# ioshield.net
KiCad netlist of a schematic drawn in EAGLE
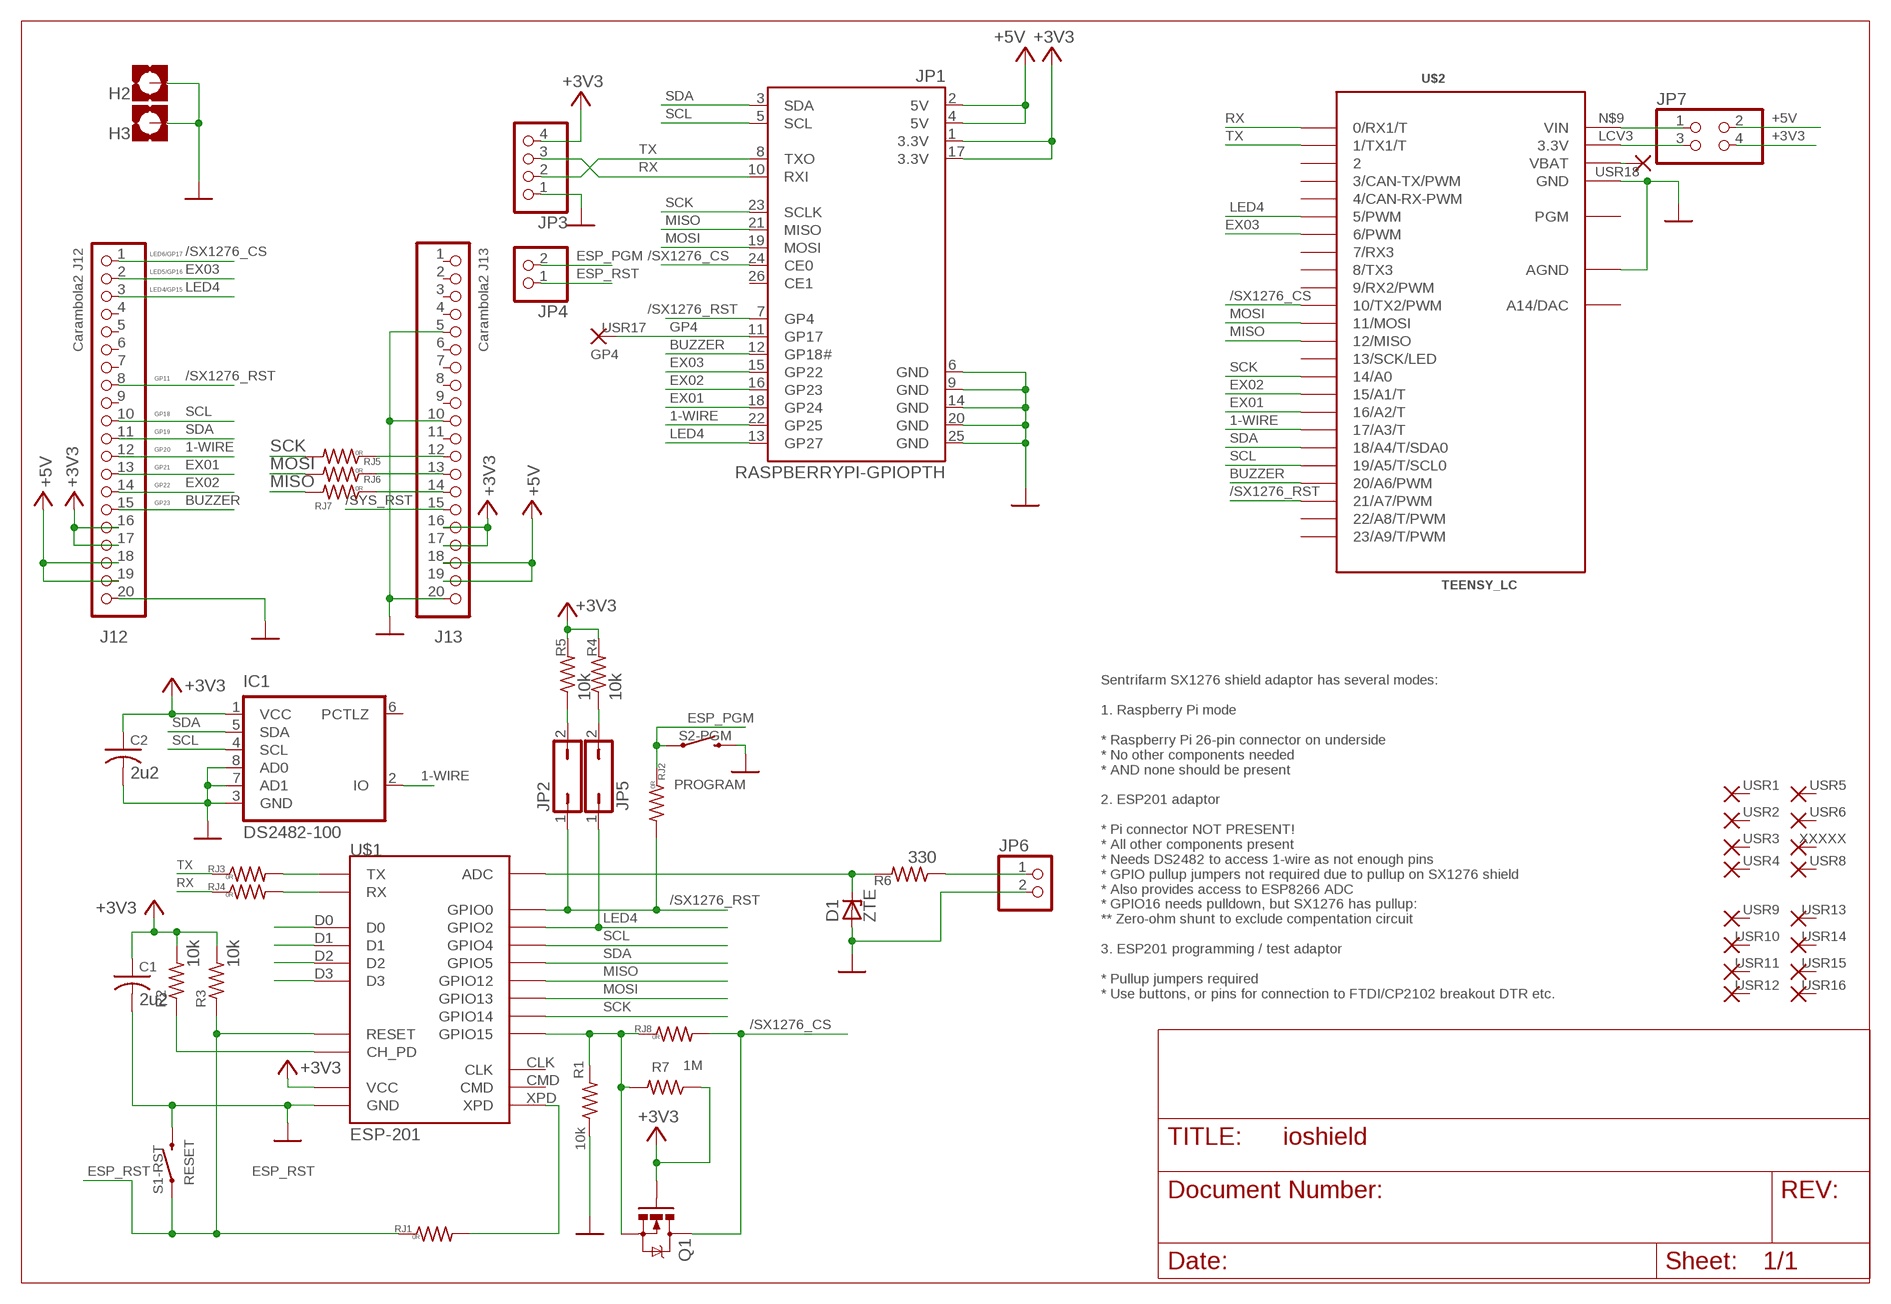
[diagram p0: schematic, sheet 1]

(export (version "E")
  (design (tool "Eeschema 10.0.6"))
  (components
    (comp (ref "C1")
      (value "2u2")
      (footprint "eagle-import:C1206")
      (libsource (lib "eagle-import") (part "C-USC1206"))
    )
    (comp (ref "C2")
      (value "2u2")
      (footprint "eagle-import:C1206")
      (libsource (lib "eagle-import") (part "C-USC1206"))
    )
    (comp (ref "D1")
      (value "ZTE")
      (footprint "eagle-import:DO35Z10")
      (libsource (lib "eagle-import") (part "ZTE"))
    )
    (comp (ref "H2")
      (value "MOUNT-PAD-SQUARE3.2")
      (footprint "eagle-import:3,2-PAD-SQUARE")
      (libsource (lib "eagle-import") (part "MOUNT-PAD-SQUARE3.2"))
    )
    (comp (ref "H3")
      (value "MOUNT-PAD-SQUARE3.2")
      (footprint "eagle-import:3,2-PAD-SQUARE")
      (libsource (lib "eagle-import") (part "MOUNT-PAD-SQUARE3.2"))
    )
    (comp (ref "IC1")
      (value "DS2482-100")
      (footprint "eagle-import:SO08")
      (libsource (lib "eagle-import") (part "DS2482-100"))
    )
    (comp (ref "J12")
      (value "Carambola2 J12")
      (footprint "eagle-import:1X20")
      (libsource (lib "eagle-import") (part "PINHD-1X20"))
    )
    (comp (ref "J13")
      (value "Carambola2 J13")
      (footprint "eagle-import:1X20")
      (libsource (lib "eagle-import") (part "PINHD-1X20"))
    )
    (comp (ref "JP1")
      (value "RASPBERRYPI-GPIOPTH")
      (footprint "eagle-import:2X13-SHROUDED")
      (libsource (lib "eagle-import") (part "RASPBERRYPI-GPIOPTH"))
    )
    (comp (ref "JP2")
      (value "JP1Q")
      (footprint "eagle-import:JP1")
      (libsource (lib "eagle-import") (part "JP1Q"))
    )
    (comp (ref "JP3")
      (value "PINHD-1X4")
      (footprint "eagle-import:1X04")
      (libsource (lib "eagle-import") (part "PINHD-1X4"))
    )
    (comp (ref "JP4")
      (value "PINHD-1X2")
      (footprint "eagle-import:1X02")
      (libsource (lib "eagle-import") (part "PINHD-1X2"))
    )
    (comp (ref "JP5")
      (value "JP1Q")
      (footprint "eagle-import:JP1")
      (libsource (lib "eagle-import") (part "JP1Q"))
    )
    (comp (ref "JP6")
      (value "PINHD-1X2")
      (footprint "eagle-import:1X02")
      (libsource (lib "eagle-import") (part "PINHD-1X2"))
    )
    (comp (ref "JP7")
      (value "PINHD-2X2")
      (footprint "eagle-import:2X02")
      (libsource (lib "eagle-import") (part "PINHD-2X2"))
    )
    (comp (ref "Q1")
      (value "MOSFET-NCHANNEL2N7000")
      (footprint "eagle-import:TO-92")
      (libsource (lib "eagle-import") (part "MOSFET-NCHANNEL2N7000"))
    )
    (comp (ref "R1")
      (value "10k")
      (footprint "eagle-import:M1206")
      (libsource (lib "eagle-import") (part "R-US_M1206"))
    )
    (comp (ref "R2")
      (value "10k")
      (footprint "eagle-import:M1206")
      (libsource (lib "eagle-import") (part "R-US_M1206"))
    )
    (comp (ref "R3")
      (value "10k")
      (footprint "eagle-import:M1206")
      (libsource (lib "eagle-import") (part "R-US_M1206"))
    )
    (comp (ref "R4")
      (value "10k")
      (footprint "eagle-import:M1206")
      (libsource (lib "eagle-import") (part "R-US_M1206"))
    )
    (comp (ref "R5")
      (value "10k")
      (footprint "eagle-import:M1206")
      (libsource (lib "eagle-import") (part "R-US_M1206"))
    )
    (comp (ref "R6")
      (value "330")
      (footprint "eagle-import:M1206")
      (libsource (lib "eagle-import") (part "R-US_M1206"))
    )
    (comp (ref "R7")
      (value "1M")
      (footprint "eagle-import:M1206")
      (libsource (lib "eagle-import") (part "R-US_M1206"))
    )
    (comp (ref "RJ1")
      (value "0R")
      (footprint "eagle-import:M1206")
      (libsource (lib "eagle-import") (part "R-US_M1206"))
    )
    (comp (ref "RJ2")
      (value "0R")
      (footprint "eagle-import:M1206")
      (libsource (lib "eagle-import") (part "R-US_M1206"))
    )
    (comp (ref "RJ3")
      (value "0R")
      (footprint "eagle-import:M1206")
      (libsource (lib "eagle-import") (part "R-US_M1206"))
    )
    (comp (ref "RJ4")
      (value "0R")
      (footprint "eagle-import:M1206")
      (libsource (lib "eagle-import") (part "R-US_M1206"))
    )
    (comp (ref "RJ5")
      (value "0R")
      (footprint "eagle-import:M1206")
      (libsource (lib "eagle-import") (part "R-US_M1206"))
    )
    (comp (ref "RJ6")
      (value "0R")
      (footprint "eagle-import:M1206")
      (libsource (lib "eagle-import") (part "R-US_M1206"))
    )
    (comp (ref "RJ7")
      (value "0R")
      (footprint "eagle-import:M1206")
      (libsource (lib "eagle-import") (part "R-US_M1206"))
    )
    (comp (ref "RJ8")
      (value "0R")
      (footprint "eagle-import:M1206")
      (libsource (lib "eagle-import") (part "R-US_M1206"))
    )
    (comp (ref "S1-RST")
      (value "SWITCH-MOMENTARY-2PTH")
      (footprint "eagle-import:TACTILE-PTH")
      (libsource (lib "eagle-import") (part "SWITCH-MOMENTARY-2PTH"))
    )
    (comp (ref "S2-PGM")
      (value "SWITCH-MOMENTARY-2PTH")
      (footprint "eagle-import:TACTILE-PTH")
      (libsource (lib "eagle-import") (part "SWITCH-MOMENTARY-2PTH"))
    )
    (comp (ref "U$1")
      (value "ESP-201")
      (footprint "eagle-import:ESP-201")
      (libsource (lib "eagle-import") (part "ESP-201"))
    )
    (comp (ref "U$2")
      (value "TEENSY_LC")
      (footprint "eagle-import:TEENSY_3.1_BASIC")
      (libsource (lib "eagle-import") (part "TEENSY_3.1_BASIC"))
    )
    (comp (ref "USR1")
      (value "1,6/0,8")
      (footprint "eagle-import:1,6_0,8")
      (libsource (lib "eagle-import") (part "1,6/0,8"))
    )
    (comp (ref "USR2")
      (value "1,6/0,8")
      (footprint "eagle-import:1,6_0,8")
      (libsource (lib "eagle-import") (part "1,6/0,8"))
    )
    (comp (ref "USR3")
      (value "1,6/0,8")
      (footprint "eagle-import:1,6_0,8")
      (libsource (lib "eagle-import") (part "1,6/0,8"))
    )
    (comp (ref "USR4")
      (value "1,6/0,8")
      (footprint "eagle-import:1,6_0,8")
      (libsource (lib "eagle-import") (part "1,6/0,8"))
    )
    (comp (ref "USR5")
      (value "1,6/0,8")
      (footprint "eagle-import:1,6_0,8")
      (libsource (lib "eagle-import") (part "1,6/0,8"))
    )
    (comp (ref "USR6")
      (value "1,6/0,8")
      (footprint "eagle-import:1,6_0,8")
      (libsource (lib "eagle-import") (part "1,6/0,8"))
    )
    (comp (ref "USR8")
      (value "1,6/0,8")
      (footprint "eagle-import:1,6_0,8")
      (libsource (lib "eagle-import") (part "1,6/0,8"))
    )
    (comp (ref "USR9")
      (value "1,6/0,8")
      (footprint "eagle-import:1,6_0,8")
      (libsource (lib "eagle-import") (part "1,6/0,8"))
    )
    (comp (ref "USR10")
      (value "1,6/0,8")
      (footprint "eagle-import:1,6_0,8")
      (libsource (lib "eagle-import") (part "1,6/0,8"))
    )
    (comp (ref "USR11")
      (value "1,6/0,8")
      (footprint "eagle-import:1,6_0,8")
      (libsource (lib "eagle-import") (part "1,6/0,8"))
    )
    (comp (ref "USR12")
      (value "1,6/0,8")
      (footprint "eagle-import:1,6_0,8")
      (libsource (lib "eagle-import") (part "1,6/0,8"))
    )
    (comp (ref "USR13")
      (value "1,6/0,8")
      (footprint "eagle-import:1,6_0,8")
      (libsource (lib "eagle-import") (part "1,6/0,8"))
    )
    (comp (ref "USR14")
      (value "1,6/0,8")
      (footprint "eagle-import:1,6_0,8")
      (libsource (lib "eagle-import") (part "1,6/0,8"))
    )
    (comp (ref "USR15")
      (value "1,6/0,8")
      (footprint "eagle-import:1,6_0,8")
      (libsource (lib "eagle-import") (part "1,6/0,8"))
    )
    (comp (ref "USR16")
      (value "1,6/0,8")
      (footprint "eagle-import:1,6_0,8")
      (libsource (lib "eagle-import") (part "1,6/0,8"))
    )
    (comp (ref "USR17")
      (value "GP4")
      (footprint "eagle-import:1,6_0,8")
      (libsource (lib "eagle-import") (part "1,6/0,8"))
    )
    (comp (ref "USR18")
      (value "1,6/0,8")
      (footprint "eagle-import:1,6_0,8")
      (libsource (lib "eagle-import") (part "1,6/0,8"))
    )
    (comp (ref "XXXXX")
      (value "1,6/0,8")
      (footprint "eagle-import:1,6_0,8")
      (libsource (lib "eagle-import") (part "1,6/0,8"))
    )
  )
  (nets
    (net (code "1") (name "+3V3") (class "Default")
      (node (ref "C1") (pin "1") (pinfunction "1_1") (pintype "passive"))
      (node (ref "C2") (pin "1") (pinfunction "1_1") (pintype "passive"))
      (node (ref "IC1") (pin "1") (pinfunction "VCC_1") (pintype "power_in"))
      (node (ref "J12") (pin "16") (pinfunction "16_16") (pintype "passive"))
      (node (ref "J12") (pin "17") (pinfunction "17_17") (pintype "passive"))
      (node (ref "J13") (pin "16") (pinfunction "16_16") (pintype "passive"))
      (node (ref "J13") (pin "17") (pinfunction "17_17") (pintype "passive"))
      (node (ref "JP1") (pin "1") (pinfunction "3.3V_1") (pintype "power_in"))
      (node (ref "JP1") (pin "17") (pinfunction "3.3V_17") (pintype "power_in"))
      (node (ref "JP3") (pin "4") (pinfunction "4_4") (pintype "passive"))
      (node (ref "JP7") (pin "4") (pinfunction "4_4") (pintype "passive"))
      (node (ref "Q1") (pin "2") (pinfunction "G_2") (pintype "passive"))
      (node (ref "R2") (pin "2") (pinfunction "2_2") (pintype "passive"))
      (node (ref "R3") (pin "2") (pinfunction "2_2") (pintype "passive"))
      (node (ref "R4") (pin "2") (pinfunction "2_2") (pintype "passive"))
      (node (ref "R5") (pin "2") (pinfunction "2_2") (pintype "passive"))
      (node (ref "R7") (pin "1") (pinfunction "1_1") (pintype "passive"))
      (node (ref "U$1") (pin "3V3") (pinfunction "VCC_3V3") (pintype "bidirectional"))
      (node (ref "U$1") (pin "3V3_2") (pinfunction "VCC_3V3_2") (pintype "bidirectional"))
      (node (ref "U$1") (pin "3V3_3") (pinfunction "VCC_3V3_3") (pintype "bidirectional"))
    )
    (net (code "2") (name "+5V") (class "Default")
      (node (ref "J12") (pin "18") (pinfunction "18_18") (pintype "passive"))
      (node (ref "J12") (pin "19") (pinfunction "19_19") (pintype "passive"))
      (node (ref "J13") (pin "18") (pinfunction "18_18") (pintype "passive"))
      (node (ref "J13") (pin "19") (pinfunction "19_19") (pintype "passive"))
      (node (ref "JP1") (pin "2") (pinfunction "5V_2") (pintype "power_in"))
      (node (ref "JP1") (pin "4") (pinfunction "5V_4") (pintype "power_in"))
      (node (ref "JP7") (pin "2") (pinfunction "2_2") (pintype "passive"))
    )
    (net (code "3") (name "/1-WIRE") (class "Default")
      (node (ref "IC1") (pin "2") (pinfunction "IO_2") (pintype "bidirectional"))
      (node (ref "J12") (pin "12") (pinfunction "12_12") (pintype "passive"))
      (node (ref "JP1") (pin "22") (pinfunction "GP25_22") (pintype "bidirectional"))
      (node (ref "U$2") (pin "17/A3") (pinfunction "17/A3/T_17/A3") (pintype "bidirectional"))
    )
    (net (code "4") (name "/BUZZER") (class "Default")
      (node (ref "J12") (pin "15") (pinfunction "15_15") (pintype "passive"))
      (node (ref "JP1") (pin "12") (pinfunction "GP18#_12") (pintype "bidirectional"))
      (node (ref "U$2") (pin "20/A6") (pinfunction "20/A6/PWM_20/A6") (pintype "bidirectional"))
    )
    (net (code "5") (name "/ESP_PGM") (class "Default")
      (node (ref "JP4") (pin "2") (pinfunction "2_2") (pintype "passive"))
      (node (ref "RJ2") (pin "1") (pinfunction "1_1") (pintype "passive"))
      (node (ref "S2-PGM") (pin "1") (pinfunction "1_1") (pintype "passive"))
    )
    (net (code "6") (name "/ESP_RST") (class "Default")
      (node (ref "JP4") (pin "1") (pinfunction "1_1") (pintype "passive"))
      (node (ref "R3") (pin "1") (pinfunction "1_1") (pintype "passive"))
      (node (ref "RJ1") (pin "1") (pinfunction "1_1") (pintype "passive"))
      (node (ref "S1-RST") (pin "1") (pinfunction "1_1") (pintype "passive"))
      (node (ref "U$1") (pin "RST") (pinfunction "RESET_RST") (pintype "bidirectional"))
    )
    (net (code "7") (name "/EX01") (class "Default")
      (node (ref "J12") (pin "13") (pinfunction "13_13") (pintype "passive"))
      (node (ref "JP1") (pin "18") (pinfunction "GP24_18") (pintype "bidirectional"))
      (node (ref "U$2") (pin "16/A2") (pinfunction "16/A2/T_16/A2") (pintype "bidirectional"))
    )
    (net (code "8") (name "/EX02") (class "Default")
      (node (ref "J12") (pin "14") (pinfunction "14_14") (pintype "passive"))
      (node (ref "JP1") (pin "16") (pinfunction "GP23_16") (pintype "bidirectional"))
      (node (ref "U$2") (pin "15/A1") (pinfunction "15/A1/T_15/A1") (pintype "bidirectional"))
    )
    (net (code "9") (name "/EX03") (class "Default")
      (node (ref "J12") (pin "2") (pinfunction "2_2") (pintype "passive"))
      (node (ref "JP1") (pin "15") (pinfunction "GP22_15") (pintype "bidirectional"))
      (node (ref "U$2") (pin "6") (pinfunction "6/PWM_6") (pintype "bidirectional"))
    )
    (net (code "10") (name "/GP4") (class "Default")
      (node (ref "JP1") (pin "11") (pinfunction "GP17_11") (pintype "bidirectional"))
      (node (ref "USR17") (pin "1") (pinfunction "P_1") (pintype "passive"))
    )
    (net (code "11") (name "/LCV3") (class "Default")
      (node (ref "JP7") (pin "3") (pinfunction "3_3") (pintype "passive"))
      (node (ref "U$2") (pin "3.3V") (pinfunction "3.3V_3.3V") (pintype "power_in"))
      (node (ref "U$2") (pin "3.3V1") (pinfunction "3.3V_3.3V1") (pintype "power_in"))
    )
    (net (code "12") (name "/LED4") (class "Default")
      (node (ref "J12") (pin "3") (pinfunction "3_3") (pintype "passive"))
      (node (ref "JP1") (pin "13") (pinfunction "GP27_13") (pintype "bidirectional"))
      (node (ref "JP5") (pin "1") (pinfunction "1_1") (pintype "passive"))
      (node (ref "U$1") (pin "GPIO2") (pinfunction "GPIO2_GPIO2") (pintype "bidirectional"))
      (node (ref "U$2") (pin "5") (pinfunction "5/PWM_5") (pintype "bidirectional"))
    )
    (net (code "13") (name "/MISO") (class "Default")
      (node (ref "JP1") (pin "21") (pinfunction "MISO_21") (pintype "input"))
      (node (ref "RJ7") (pin "2") (pinfunction "2_2") (pintype "passive"))
      (node (ref "U$1") (pin "GPIO12") (pinfunction "GPIO12_GPIO12") (pintype "bidirectional"))
      (node (ref "U$2") (pin "12") (pinfunction "12/MISO_12") (pintype "bidirectional"))
    )
    (net (code "14") (name "/MOSI") (class "Default")
      (node (ref "JP1") (pin "19") (pinfunction "MOSI_19") (pintype "output"))
      (node (ref "RJ6") (pin "2") (pinfunction "2_2") (pintype "passive"))
      (node (ref "U$1") (pin "GPIO13") (pinfunction "GPIO13_GPIO13") (pintype "bidirectional"))
      (node (ref "U$2") (pin "11") (pinfunction "11/MOSI_11") (pintype "bidirectional"))
    )
    (net (code "15") (name "/N$9") (class "Default")
      (node (ref "JP7") (pin "1") (pinfunction "1_1") (pintype "passive"))
      (node (ref "U$2") (pin "VIN") (pinfunction "VIN_VIN") (pintype "power_in"))
    )
    (net (code "16") (name "/RX") (class "Default")
      (node (ref "JP1") (pin "10") (pinfunction "RXI_10") (pintype "input"))
      (node (ref "JP3") (pin "3") (pinfunction "3_3") (pintype "passive"))
      (node (ref "RJ4") (pin "1") (pinfunction "1_1") (pintype "passive"))
      (node (ref "U$2") (pin "0") (pinfunction "0/RX1/T_0") (pintype "bidirectional"))
    )
    (net (code "17") (name "/SCK") (class "Default")
      (node (ref "JP1") (pin "23") (pinfunction "SCLK_23") (pintype "output"))
      (node (ref "RJ5") (pin "2") (pinfunction "2_2") (pintype "passive"))
      (node (ref "U$1") (pin "GPIO14") (pinfunction "GPIO14_GPIO14") (pintype "bidirectional"))
      (node (ref "U$2") (pin "14/A0") (pinfunction "14/A0_14/A0") (pintype "bidirectional"))
    )
    (net (code "18") (name "/SCL") (class "Default")
      (node (ref "IC1") (pin "4") (pinfunction "SCL_4") (pintype "input"))
      (node (ref "J12") (pin "10") (pinfunction "10_10") (pintype "passive"))
      (node (ref "JP1") (pin "5") (pinfunction "SCL_5") (pintype "bidirectional"))
      (node (ref "U$1") (pin "GPIO4") (pinfunction "GPIO4_GPIO4") (pintype "bidirectional"))
      (node (ref "U$2") (pin "19/A5") (pinfunction "19/A5/T/SCL0_19/A5") (pintype "bidirectional"))
    )
    (net (code "19") (name "/SDA") (class "Default")
      (node (ref "IC1") (pin "5") (pinfunction "SDA_5") (pintype "input"))
      (node (ref "J12") (pin "11") (pinfunction "11_11") (pintype "passive"))
      (node (ref "JP1") (pin "3") (pinfunction "SDA_3") (pintype "bidirectional"))
      (node (ref "U$1") (pin "GPIO5") (pinfunction "GPIO5_GPIO5") (pintype "bidirectional"))
      (node (ref "U$2") (pin "18/A4") (pinfunction "18/A4/T/SDA0_18/A4") (pintype "bidirectional"))
    )
    (net (code "20") (name "/TX") (class "Default")
      (node (ref "JP1") (pin "8") (pinfunction "TXO_8") (pintype "output"))
      (node (ref "JP3") (pin "2") (pinfunction "2_2") (pintype "passive"))
      (node (ref "RJ3") (pin "1") (pinfunction "1_1") (pintype "passive"))
      (node (ref "U$2") (pin "1") (pinfunction "1/TX1/T_1") (pintype "bidirectional"))
    )
    (net (code "21") (name "/{slash}SX1276_CS") (class "Default")
      (node (ref "J12") (pin "1") (pinfunction "1_1") (pintype "passive"))
      (node (ref "JP1") (pin "24") (pinfunction "CE0_24") (pintype "output"))
      (node (ref "Q1") (pin "3") (pinfunction "D_3") (pintype "passive"))
      (node (ref "RJ8") (pin "2") (pinfunction "2_2") (pintype "passive"))
      (node (ref "U$2") (pin "10") (pinfunction "10/TX2/PWM_10") (pintype "bidirectional"))
    )
    (net (code "22") (name "/{slash}SX1276_RST") (class "Default")
      (node (ref "J12") (pin "8") (pinfunction "8_8") (pintype "passive"))
      (node (ref "JP1") (pin "7") (pinfunction "GP4_7") (pintype "bidirectional"))
      (node (ref "JP2") (pin "1") (pinfunction "1_1") (pintype "passive"))
      (node (ref "RJ2") (pin "2") (pinfunction "2_2") (pintype "passive"))
      (node (ref "U$1") (pin "GPIO0") (pinfunction "GPIO0_GPIO0") (pintype "bidirectional"))
      (node (ref "U$2") (pin "21/A7") (pinfunction "21/A7/PWM_21/A7") (pintype "bidirectional"))
    )
    (net (code "23") (name "/{slash}SYS_RST") (class "Default")
      (node (ref "J13") (pin "15") (pinfunction "15_15") (pintype "passive"))
    )
    (net (code "24") (name "GND") (class "Default")
      (node (ref "C1") (pin "2") (pinfunction "2_2") (pintype "passive"))
      (node (ref "C2") (pin "2") (pinfunction "2_2") (pintype "passive"))
      (node (ref "D1") (pin "A") (pinfunction "A_A") (pintype "passive"))
      (node (ref "H2") (pin "B3,2") (pinfunction "MOUNT_B3,2") (pintype "passive"))
      (node (ref "H3") (pin "B3,2") (pinfunction "MOUNT_B3,2") (pintype "passive"))
      (node (ref "IC1") (pin "3") (pinfunction "GND_3") (pintype "power_in"))
      (node (ref "IC1") (pin "7") (pinfunction "AD1_7") (pintype "bidirectional"))
      (node (ref "IC1") (pin "8") (pinfunction "AD0_8") (pintype "bidirectional"))
      (node (ref "J12") (pin "20") (pinfunction "20_20") (pintype "passive"))
      (node (ref "J13") (pin "10") (pinfunction "10_10") (pintype "passive"))
      (node (ref "J13") (pin "20") (pinfunction "20_20") (pintype "passive"))
      (node (ref "J13") (pin "5") (pinfunction "5_5") (pintype "passive"))
      (node (ref "JP1") (pin "14") (pinfunction "GND_14") (pintype "power_in"))
      (node (ref "JP1") (pin "20") (pinfunction "GND_20") (pintype "power_in"))
      (node (ref "JP1") (pin "25") (pinfunction "GND_25") (pintype "power_in"))
      (node (ref "JP1") (pin "6") (pinfunction "GND_6") (pintype "power_in"))
      (node (ref "JP1") (pin "9") (pinfunction "GND_9") (pintype "power_in"))
      (node (ref "JP3") (pin "1") (pinfunction "1_1") (pintype "passive"))
      (node (ref "JP6") (pin "2") (pinfunction "2_2") (pintype "passive"))
      (node (ref "R1") (pin "1") (pinfunction "1_1") (pintype "passive"))
      (node (ref "S1-RST") (pin "3") (pinfunction "2_3") (pintype "passive"))
      (node (ref "S2-PGM") (pin "3") (pinfunction "2_3") (pintype "passive"))
      (node (ref "U$1") (pin "GND") (pinfunction "GND_GND") (pintype "bidirectional"))
      (node (ref "U$1") (pin "GND_2") (pinfunction "GND_GND_2") (pintype "bidirectional"))
      (node (ref "U$1") (pin "GND_3") (pinfunction "GND_GND_3") (pintype "bidirectional"))
      (node (ref "U$2") (pin "AGND") (pinfunction "AGND_AGND") (pintype "power_in"))
      (node (ref "U$2") (pin "GND") (pinfunction "GND_GND") (pintype "power_in"))
      (node (ref "U$2") (pin "GND1") (pinfunction "GND_GND1") (pintype "power_in"))
    )
    (net (code "25") (name "Net-(D1-PadC)") (class "Default")
      (node (ref "D1") (pin "C") (pinfunction "C_C") (pintype "passive"))
      (node (ref "R6") (pin "2") (pinfunction "2_2") (pintype "passive"))
      (node (ref "U$1") (pin "ADC") (pinfunction "ADC_ADC") (pintype "bidirectional"))
    )
    (net (code "26") (name "Net-(J13-Pad12)") (class "Default")
      (node (ref "J13") (pin "12") (pinfunction "12_12") (pintype "passive"))
      (node (ref "RJ5") (pin "1") (pinfunction "1_1") (pintype "passive"))
    )
    (net (code "27") (name "Net-(J13-Pad13)") (class "Default")
      (node (ref "J13") (pin "13") (pinfunction "13_13") (pintype "passive"))
      (node (ref "RJ6") (pin "1") (pinfunction "1_1") (pintype "passive"))
    )
    (net (code "28") (name "Net-(J13-Pad14)") (class "Default")
      (node (ref "J13") (pin "14") (pinfunction "14_14") (pintype "passive"))
      (node (ref "RJ7") (pin "1") (pinfunction "1_1") (pintype "passive"))
    )
    (net (code "29") (name "Net-(JP2-Pad2)") (class "Default")
      (node (ref "JP2") (pin "2") (pinfunction "2_2") (pintype "passive"))
      (node (ref "R5") (pin "1") (pinfunction "1_1") (pintype "passive"))
    )
    (net (code "30") (name "Net-(JP5-Pad2)") (class "Default")
      (node (ref "JP5") (pin "2") (pinfunction "2_2") (pintype "passive"))
      (node (ref "R4") (pin "1") (pinfunction "1_1") (pintype "passive"))
    )
    (net (code "31") (name "Net-(JP6-Pad1)") (class "Default")
      (node (ref "JP6") (pin "1") (pinfunction "1_1") (pintype "passive"))
      (node (ref "R6") (pin "1") (pinfunction "1_1") (pintype "passive"))
    )
    (net (code "32") (name "Net-(Q1-S)") (class "Default")
      (node (ref "Q1") (pin "1") (pinfunction "S_1") (pintype "passive"))
      (node (ref "R1") (pin "2") (pinfunction "2_2") (pintype "passive"))
      (node (ref "R7") (pin "2") (pinfunction "2_2") (pintype "passive"))
      (node (ref "RJ8") (pin "1") (pinfunction "1_1") (pintype "passive"))
      (node (ref "U$1") (pin "GPIO15") (pinfunction "GPIO15_GPIO15") (pintype "bidirectional"))
    )
    (net (code "33") (name "Net-(R2-Pad1)") (class "Default")
      (node (ref "R2") (pin "1") (pinfunction "1_1") (pintype "passive"))
      (node (ref "U$1") (pin "CH_PD") (pinfunction "CH_PD_CH_PD") (pintype "bidirectional"))
    )
    (net (code "34") (name "Net-(RJ1-Pad2)") (class "Default")
      (node (ref "RJ1") (pin "2") (pinfunction "2_2") (pintype "passive"))
      (node (ref "U$1") (pin "XPD") (pinfunction "XPD_XPD") (pintype "bidirectional"))
    )
    (net (code "35") (name "Net-(USR18-P)") (class "Default")
      (node (ref "U$2") (pin "VBAT") (pinfunction "VBAT_VBAT") (pintype "power_in"))
      (node (ref "USR18") (pin "1") (pinfunction "P_1") (pintype "passive"))
    )
    (net (code "36") (name "unconnected-(IC1-PCTLZ-Pad6)") (class "Default")
      (node (ref "IC1") (pin "6") (pinfunction "PCTLZ_6") (pintype "output"))
    )
    (net (code "37") (name "unconnected-(J12-Pad4)") (class "Default")
      (node (ref "J12") (pin "4") (pinfunction "4_4") (pintype "passive"))
    )
    (net (code "38") (name "unconnected-(J12-Pad5)") (class "Default")
      (node (ref "J12") (pin "5") (pinfunction "5_5") (pintype "passive"))
    )
    (net (code "39") (name "unconnected-(J12-Pad6)") (class "Default")
      (node (ref "J12") (pin "6") (pinfunction "6_6") (pintype "passive"))
    )
    (net (code "40") (name "unconnected-(J12-Pad7)") (class "Default")
      (node (ref "J12") (pin "7") (pinfunction "7_7") (pintype "passive"))
    )
    (net (code "41") (name "unconnected-(J12-Pad9)") (class "Default")
      (node (ref "J12") (pin "9") (pinfunction "9_9") (pintype "passive"))
    )
    (net (code "42") (name "unconnected-(J13-Pad1)") (class "Default")
      (node (ref "J13") (pin "1") (pinfunction "1_1") (pintype "passive"))
    )
    (net (code "43") (name "unconnected-(J13-Pad2)") (class "Default")
      (node (ref "J13") (pin "2") (pinfunction "2_2") (pintype "passive"))
    )
    (net (code "44") (name "unconnected-(J13-Pad3)") (class "Default")
      (node (ref "J13") (pin "3") (pinfunction "3_3") (pintype "passive"))
    )
    (net (code "45") (name "unconnected-(J13-Pad4)") (class "Default")
      (node (ref "J13") (pin "4") (pinfunction "4_4") (pintype "passive"))
    )
    (net (code "46") (name "unconnected-(J13-Pad6)") (class "Default")
      (node (ref "J13") (pin "6") (pinfunction "6_6") (pintype "passive"))
    )
    (net (code "47") (name "unconnected-(J13-Pad7)") (class "Default")
      (node (ref "J13") (pin "7") (pinfunction "7_7") (pintype "passive"))
    )
    (net (code "48") (name "unconnected-(J13-Pad8)") (class "Default")
      (node (ref "J13") (pin "8") (pinfunction "8_8") (pintype "passive"))
    )
    (net (code "49") (name "unconnected-(J13-Pad9)") (class "Default")
      (node (ref "J13") (pin "9") (pinfunction "9_9") (pintype "passive"))
    )
    (net (code "50") (name "unconnected-(J13-Pad11)") (class "Default")
      (node (ref "J13") (pin "11") (pinfunction "11_11") (pintype "passive"))
    )
    (net (code "51") (name "unconnected-(JP1-CE1-Pad26)") (class "Default")
      (node (ref "JP1") (pin "26") (pinfunction "CE1_26") (pintype "output"))
    )
    (net (code "52") (name "unconnected-(RJ3-Pad2)") (class "Default")
      (node (ref "RJ3") (pin "2") (pinfunction "2_2") (pintype "passive"))
    )
    (net (code "53") (name "unconnected-(RJ4-Pad2)") (class "Default")
      (node (ref "RJ4") (pin "2") (pinfunction "2_2") (pintype "passive"))
    )
    (net (code "54") (name "unconnected-(U$1-PadCLK)") (class "Default")
      (node (ref "U$1") (pin "CLK") (pinfunction "CLK_CLK") (pintype "bidirectional"))
    )
    (net (code "55") (name "unconnected-(U$1-PadCMD)") (class "Default")
      (node (ref "U$1") (pin "CMD") (pinfunction "CMD_CMD") (pintype "bidirectional"))
    )
    (net (code "56") (name "unconnected-(U$1-PadD0)") (class "Default")
      (node (ref "U$1") (pin "D0") (pinfunction "D0_D0") (pintype "bidirectional"))
    )
    (net (code "57") (name "unconnected-(U$1-PadD1)") (class "Default")
      (node (ref "U$1") (pin "D1") (pinfunction "D1_D1") (pintype "bidirectional"))
    )
    (net (code "58") (name "unconnected-(U$1-PadD2)") (class "Default")
      (node (ref "U$1") (pin "D2") (pinfunction "D2_D2") (pintype "bidirectional"))
    )
    (net (code "59") (name "unconnected-(U$1-PadD3)") (class "Default")
      (node (ref "U$1") (pin "D3") (pinfunction "D3_D3") (pintype "bidirectional"))
    )
    (net (code "60") (name "unconnected-(U$1-PadRX)") (class "Default")
      (node (ref "U$1") (pin "RX") (pinfunction "RX_RX") (pintype "bidirectional"))
    )
    (net (code "61") (name "unconnected-(U$1-PadTX)") (class "Default")
      (node (ref "U$1") (pin "TX") (pinfunction "TX_TX") (pintype "bidirectional"))
    )
    (net (code "62") (name "unconnected-(U$2-3{slash}CAN-TX{slash}PWM-Pad3)") (class "Default")
      (node (ref "U$2") (pin "3") (pinfunction "3/CAN-TX/PWM_3") (pintype "bidirectional"))
    )
    (net (code "63") (name "unconnected-(U$2-4{slash}CAN-RX-PWM-Pad4)") (class "Default")
      (node (ref "U$2") (pin "4") (pinfunction "4/CAN-RX-PWM_4") (pintype "bidirectional"))
    )
    (net (code "64") (name "unconnected-(U$2-7{slash}RX3-Pad7)") (class "Default")
      (node (ref "U$2") (pin "7") (pinfunction "7/RX3_7") (pintype "bidirectional"))
    )
    (net (code "65") (name "unconnected-(U$2-8{slash}TX3-Pad8)") (class "Default")
      (node (ref "U$2") (pin "8") (pinfunction "8/TX3_8") (pintype "bidirectional"))
    )
    (net (code "66") (name "unconnected-(U$2-9{slash}RX2{slash}PWM-Pad9)") (class "Default")
      (node (ref "U$2") (pin "9") (pinfunction "9/RX2/PWM_9") (pintype "bidirectional"))
    )
    (net (code "67") (name "unconnected-(U$2-13{slash}SCK{slash}LED-Pad13)") (class "Default")
      (node (ref "U$2") (pin "13") (pinfunction "13/SCK/LED_13") (pintype "bidirectional"))
    )
    (net (code "68") (name "unconnected-(U$2-22{slash}A8{slash}T{slash}PWM-Pad22{slash}A8)") (class "Default")
      (node (ref "U$2") (pin "22/A8") (pinfunction "22/A8/T/PWM_22/A8") (pintype "bidirectional"))
    )
    (net (code "69") (name "unconnected-(U$2-23{slash}A9{slash}T{slash}PWM-Pad23{slash}A9)") (class "Default")
      (node (ref "U$2") (pin "23/A9") (pinfunction "23/A9/T/PWM_23/A9") (pintype "bidirectional"))
    )
    (net (code "70") (name "unconnected-(U$2-A14{slash}DAC-PadA14)") (class "Default")
      (node (ref "U$2") (pin "A14") (pinfunction "A14/DAC_A14") (pintype "bidirectional"))
    )
    (net (code "71") (name "unconnected-(U$2-Pad2)") (class "Default")
      (node (ref "U$2") (pin "2") (pinfunction "2_2") (pintype "bidirectional"))
    )
    (net (code "72") (name "unconnected-(U$2-PadPGM)") (class "Default")
      (node (ref "U$2") (pin "PGM") (pinfunction "PGM_PGM") (pintype "bidirectional"))
    )
    (net (code "73") (name "unconnected-(USR1-P-Pad1)") (class "Default")
      (node (ref "USR1") (pin "1") (pinfunction "P_1") (pintype "passive"))
    )
    (net (code "74") (name "unconnected-(USR2-P-Pad1)") (class "Default")
      (node (ref "USR2") (pin "1") (pinfunction "P_1") (pintype "passive"))
    )
    (net (code "75") (name "unconnected-(USR3-P-Pad1)") (class "Default")
      (node (ref "USR3") (pin "1") (pinfunction "P_1") (pintype "passive"))
    )
    (net (code "76") (name "unconnected-(USR4-P-Pad1)") (class "Default")
      (node (ref "USR4") (pin "1") (pinfunction "P_1") (pintype "passive"))
    )
    (net (code "77") (name "unconnected-(USR5-P-Pad1)") (class "Default")
      (node (ref "USR5") (pin "1") (pinfunction "P_1") (pintype "passive"))
    )
    (net (code "78") (name "unconnected-(USR6-P-Pad1)") (class "Default")
      (node (ref "USR6") (pin "1") (pinfunction "P_1") (pintype "passive"))
    )
    (net (code "79") (name "unconnected-(USR8-P-Pad1)") (class "Default")
      (node (ref "USR8") (pin "1") (pinfunction "P_1") (pintype "passive"))
    )
    (net (code "80") (name "unconnected-(USR9-P-Pad1)") (class "Default")
      (node (ref "USR9") (pin "1") (pinfunction "P_1") (pintype "passive"))
    )
    (net (code "81") (name "unconnected-(USR10-P-Pad1)") (class "Default")
      (node (ref "USR10") (pin "1") (pinfunction "P_1") (pintype "passive"))
    )
    (net (code "82") (name "unconnected-(USR11-P-Pad1)") (class "Default")
      (node (ref "USR11") (pin "1") (pinfunction "P_1") (pintype "passive"))
    )
    (net (code "83") (name "unconnected-(USR12-P-Pad1)") (class "Default")
      (node (ref "USR12") (pin "1") (pinfunction "P_1") (pintype "passive"))
    )
    (net (code "84") (name "unconnected-(USR13-P-Pad1)") (class "Default")
      (node (ref "USR13") (pin "1") (pinfunction "P_1") (pintype "passive"))
    )
    (net (code "85") (name "unconnected-(USR14-P-Pad1)") (class "Default")
      (node (ref "USR14") (pin "1") (pinfunction "P_1") (pintype "passive"))
    )
    (net (code "86") (name "unconnected-(USR15-P-Pad1)") (class "Default")
      (node (ref "USR15") (pin "1") (pinfunction "P_1") (pintype "passive"))
    )
    (net (code "87") (name "unconnected-(USR16-P-Pad1)") (class "Default")
      (node (ref "USR16") (pin "1") (pinfunction "P_1") (pintype "passive"))
    )
    (net (code "88") (name "unconnected-(XXXXX-P-Pad1)") (class "Default")
      (node (ref "XXXXX") (pin "1") (pinfunction "P_1") (pintype "passive"))
    )
  )
)
